# uvir-carrier-r1-easyeda-standard-schemat.net
KiCad netlist of a schematic drawn in EasyEDA
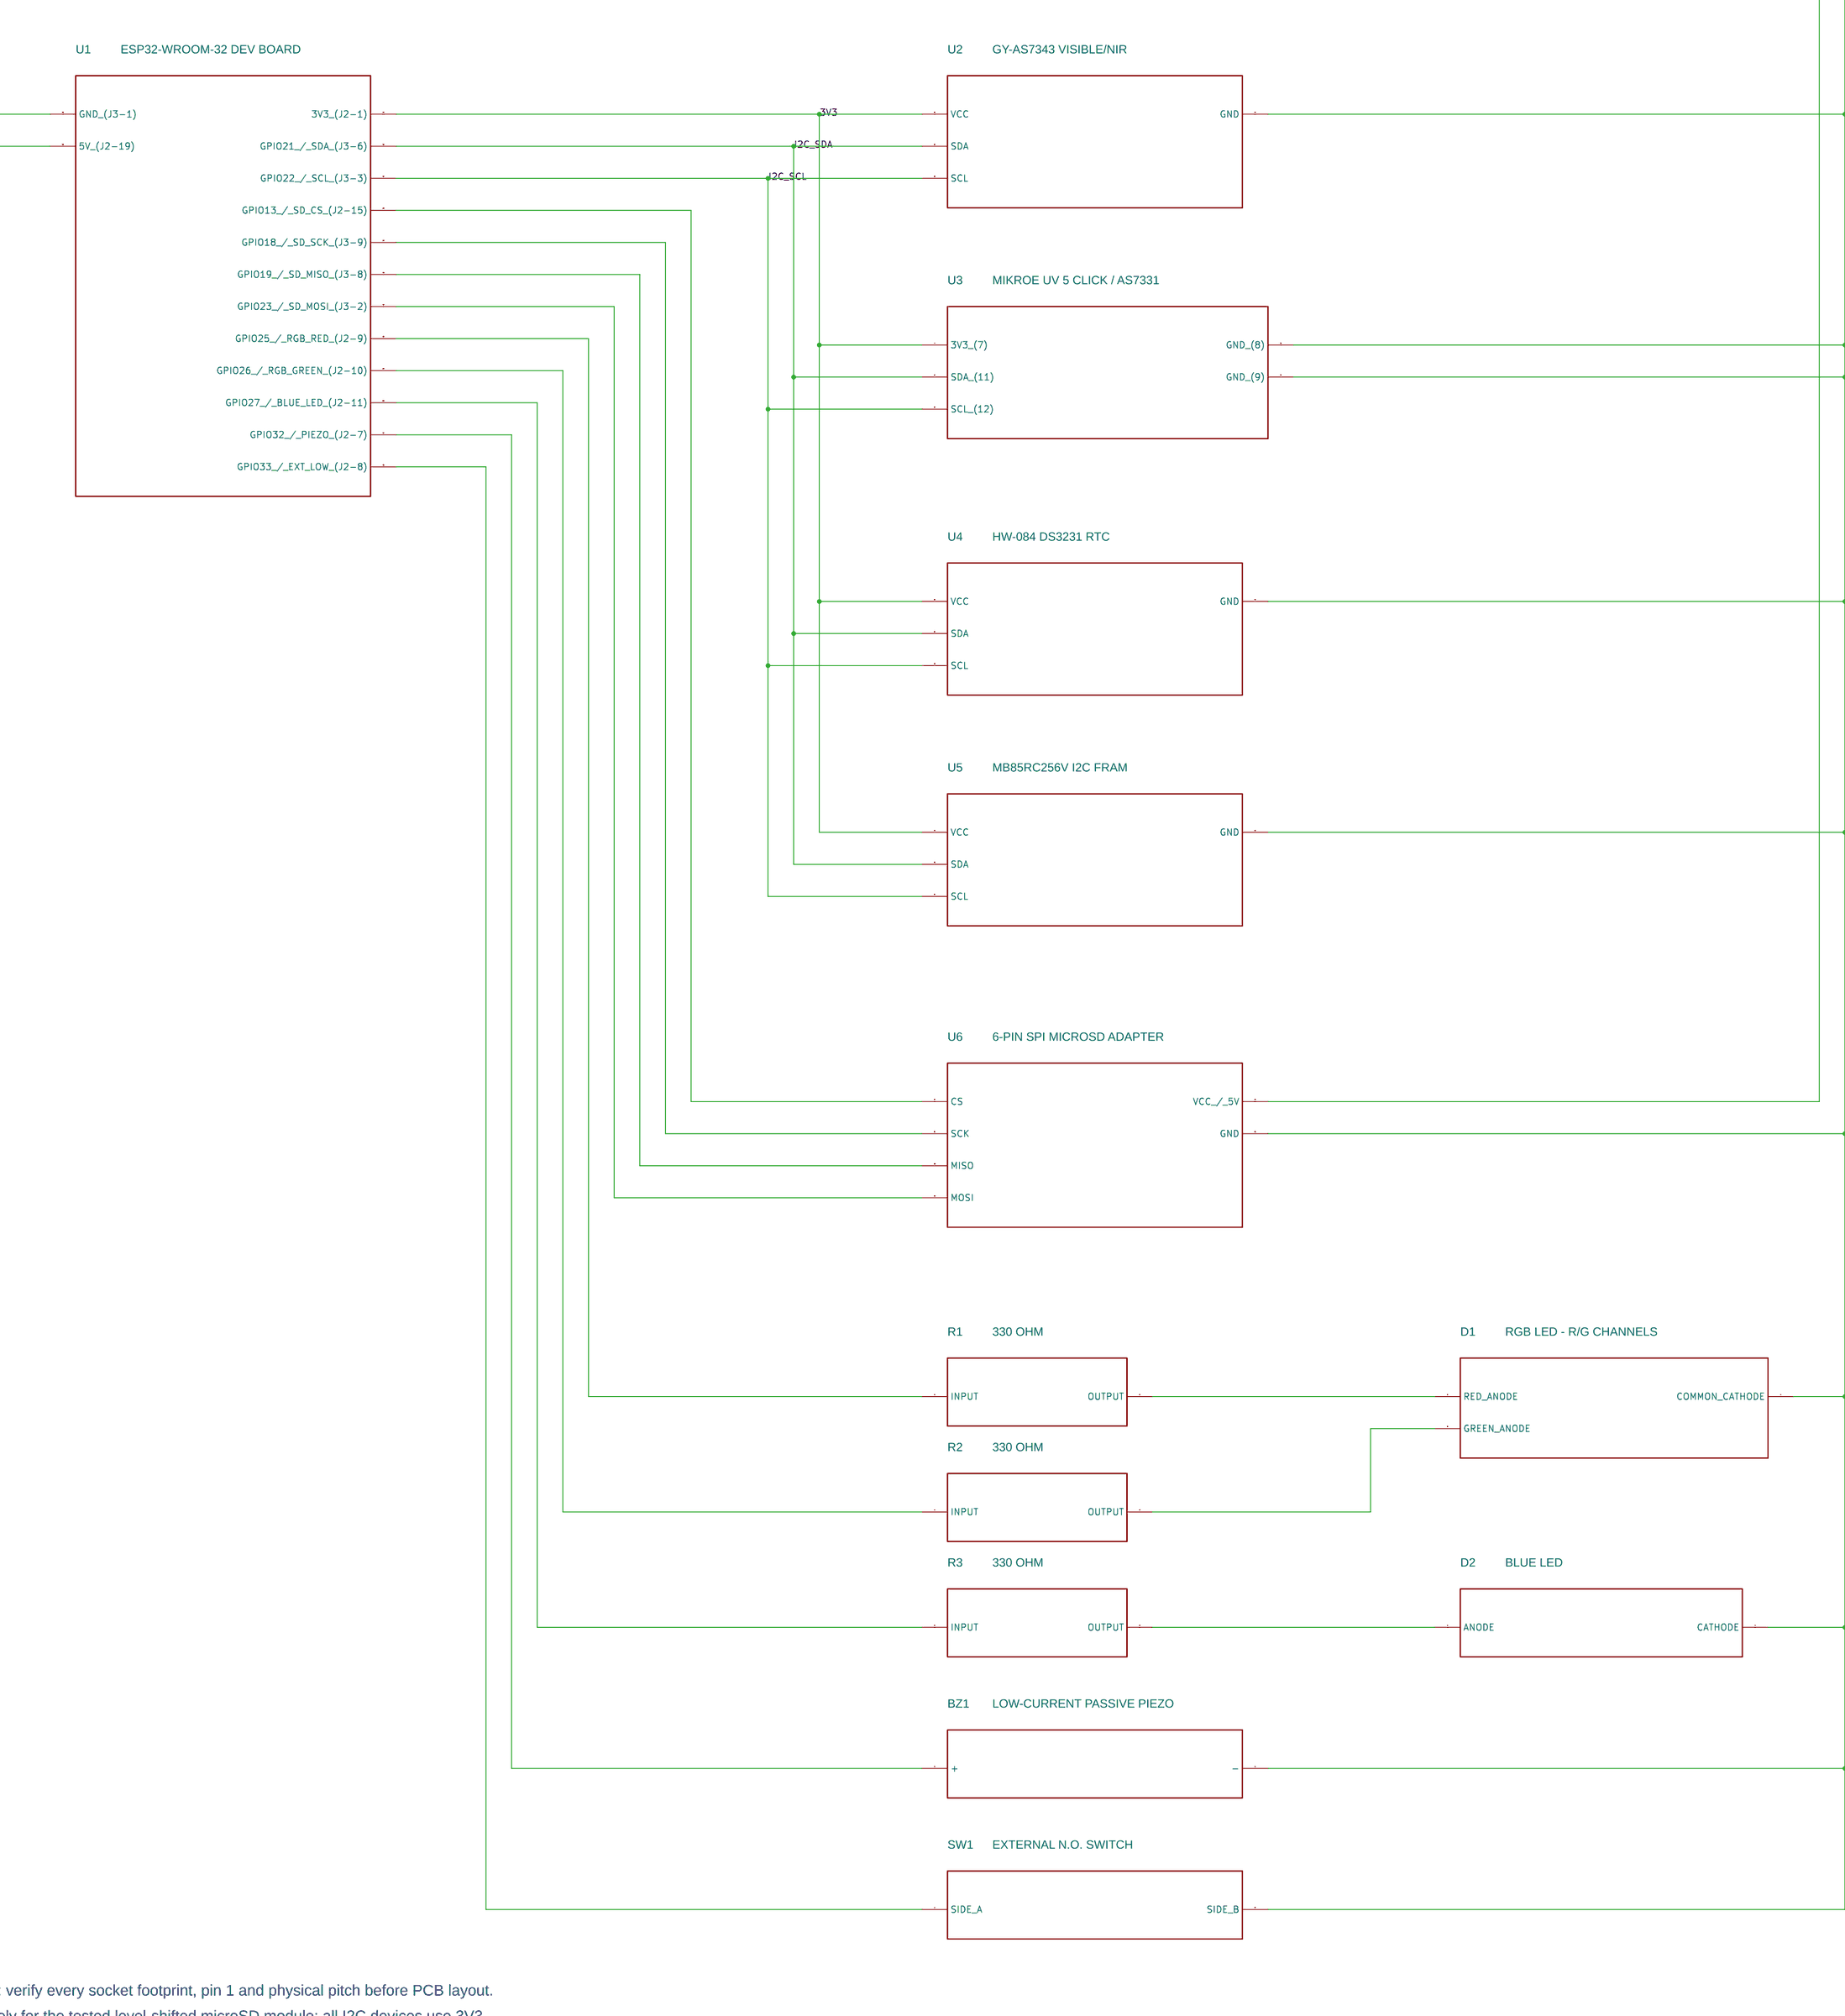
[diagram p0: schematic sheet]

(export (version "E")
  (design (tool "Eeschema 10.0.6"))
  (components
    (comp (ref "BZ1") (value "LOW-CURRENT PASSIVE PIEZO") (libsource (lib "") (part "Unknown_900_1550")))
    (comp (ref "D1") (value "RGB LED - R/G CHANNELS") (libsource (lib "") (part "Unknown_1300_1260")))
    (comp (ref "D2") (value "BLUE LED") (libsource (lib "") (part "Unknown_1300_1440")))
    (comp (ref "R1") (value "330 OHM") (libsource (lib "") (part "Unknown_900_1260")))
    (comp (ref "R2") (value "330 OHM") (libsource (lib "") (part "Unknown_900_1350")))
    (comp (ref "R3") (value "330 OHM") (libsource (lib "") (part "Unknown_900_1440")))
    (comp (ref "SW1") (value "EXTERNAL N.O. SWITCH") (libsource (lib "") (part "Unknown_900_1660")))
    (comp (ref "U1") (value "ESP32-WROOM-32 DEV BOARD") (libsource (lib "") (part "Unknown_220_260")))
    (comp (ref "U2") (value "GY-AS7343 VISIBLE/NIR") (libsource (lib "") (part "Unknown_900_260")))
    (comp (ref "U3") (value "MIKROE UV 5 CLICK / AS7331") (libsource (lib "") (part "Unknown_900_440")))
    (comp (ref "U4") (value "HW-084 DS3231 RTC") (libsource (lib "") (part "Unknown_900_640")))
    (comp (ref "U5") (value "MB85RC256V I2C FRAM") (libsource (lib "") (part "Unknown_900_820")))
    (comp (ref "U6") (value "6-PIN SPI MICROSD ADAPTER") (libsource (lib "") (part "Unknown_900_1030")))
  )
  (nets
    (net (code "1") (name "/3V3") (class "Default")
      (node (ref "U1") (pin "J2-1") (pinfunction "3V3_(J2-1)_J2-1") (pintype "unspecified"))
      (node (ref "U2") (pin "VCC") (pinfunction "VCC_VCC") (pintype "unspecified"))
      (node (ref "U3") (pin "7") (pinfunction "3V3_(7)_7") (pintype "unspecified"))
      (node (ref "U4") (pin "VCC") (pinfunction "VCC_VCC") (pintype "unspecified"))
      (node (ref "U5") (pin "VCC") (pinfunction "VCC_VCC") (pintype "unspecified"))
    )
    (net (code "2") (name "/5V_USB") (class "Default")
      (node (ref "U1") (pin "J2-19") (pinfunction "5V_(J2-19)_J2-19") (pintype "unspecified"))
      (node (ref "U6") (pin "VCC") (pinfunction "VCC_/_5V_VCC") (pintype "unspecified"))
    )
    (net (code "3") (name "/GND") (class "Default")
      (node (ref "BZ1") (pin "2") (pinfunction "-_2") (pintype "unspecified"))
      (node (ref "D1") (pin "K") (pinfunction "COMMON_CATHODE_K") (pintype "unspecified"))
      (node (ref "D2") (pin "K") (pinfunction "CATHODE_K") (pintype "unspecified"))
      (node (ref "SW1") (pin "B") (pinfunction "SIDE_B_B") (pintype "unspecified"))
      (node (ref "U1") (pin "J3-1") (pinfunction "GND_(J3-1)_J3-1") (pintype "unspecified"))
      (node (ref "U2") (pin "GND") (pinfunction "GND_GND") (pintype "unspecified"))
      (node (ref "U3") (pin "8") (pinfunction "GND_(8)_8") (pintype "unspecified"))
      (node (ref "U3") (pin "9") (pinfunction "GND_(9)_9") (pintype "unspecified"))
      (node (ref "U4") (pin "GND") (pinfunction "GND_GND") (pintype "unspecified"))
      (node (ref "U5") (pin "GND") (pinfunction "GND_GND") (pintype "unspecified"))
      (node (ref "U6") (pin "GND") (pinfunction "GND_GND") (pintype "unspecified"))
    )
    (net (code "4") (name "/I2C_SCL") (class "Default")
      (node (ref "U1") (pin "J3-3") (pinfunction "GPIO22_/_SCL_(J3-3)_J3-3") (pintype "unspecified"))
      (node (ref "U2") (pin "SCL") (pinfunction "SCL_SCL") (pintype "unspecified"))
      (node (ref "U3") (pin "12") (pinfunction "SCL_(12)_12") (pintype "unspecified"))
      (node (ref "U4") (pin "SCL") (pinfunction "SCL_SCL") (pintype "unspecified"))
      (node (ref "U5") (pin "SCL") (pinfunction "SCL_SCL") (pintype "unspecified"))
    )
    (net (code "5") (name "/I2C_SDA") (class "Default")
      (node (ref "U1") (pin "J3-6") (pinfunction "GPIO21_/_SDA_(J3-6)_J3-6") (pintype "unspecified"))
      (node (ref "U2") (pin "SDA") (pinfunction "SDA_SDA") (pintype "unspecified"))
      (node (ref "U3") (pin "11") (pinfunction "SDA_(11)_11") (pintype "unspecified"))
      (node (ref "U4") (pin "SDA") (pinfunction "SDA_SDA") (pintype "unspecified"))
      (node (ref "U5") (pin "SDA") (pinfunction "SDA_SDA") (pintype "unspecified"))
    )
    (net (code "6") (name "Net-(BZ1-+)") (class "Default")
      (node (ref "BZ1") (pin "1") (pinfunction "+_1") (pintype "unspecified"))
      (node (ref "U1") (pin "J2-7") (pinfunction "GPIO32_/_PIEZO_(J2-7)_J2-7") (pintype "unspecified"))
    )
    (net (code "7") (name "Net-(D1-GREEN_ANODE)") (class "Default")
      (node (ref "D1") (pin "G") (pinfunction "GREEN_ANODE_G") (pintype "unspecified"))
      (node (ref "R2") (pin "2") (pinfunction "OUTPUT_2") (pintype "unspecified"))
    )
    (net (code "8") (name "Net-(D1-RED_ANODE)") (class "Default")
      (node (ref "D1") (pin "R") (pinfunction "RED_ANODE_R") (pintype "unspecified"))
      (node (ref "R1") (pin "2") (pinfunction "OUTPUT_2") (pintype "unspecified"))
    )
    (net (code "9") (name "Net-(D2-ANODE)") (class "Default")
      (node (ref "D2") (pin "A") (pinfunction "ANODE_A") (pintype "unspecified"))
      (node (ref "R3") (pin "2") (pinfunction "OUTPUT_2") (pintype "unspecified"))
    )
    (net (code "10") (name "Net-(R1-INPUT)") (class "Default")
      (node (ref "R1") (pin "1") (pinfunction "INPUT_1") (pintype "unspecified"))
      (node (ref "U1") (pin "J2-9") (pinfunction "GPIO25_/_RGB_RED_(J2-9)_J2-9") (pintype "unspecified"))
    )
    (net (code "11") (name "Net-(R2-INPUT)") (class "Default")
      (node (ref "R2") (pin "1") (pinfunction "INPUT_1") (pintype "unspecified"))
      (node (ref "U1") (pin "J2-10") (pinfunction "GPIO26_/_RGB_GREEN_(J2-10)_J2-10") (pintype "unspecified"))
    )
    (net (code "12") (name "Net-(R3-INPUT)") (class "Default")
      (node (ref "R3") (pin "1") (pinfunction "INPUT_1") (pintype "unspecified"))
      (node (ref "U1") (pin "J2-11") (pinfunction "GPIO27_/_BLUE_LED_(J2-11)_J2-11") (pintype "unspecified"))
    )
    (net (code "13") (name "Net-(SW1-SIDE_A)") (class "Default")
      (node (ref "SW1") (pin "A") (pinfunction "SIDE_A_A") (pintype "unspecified"))
      (node (ref "U1") (pin "J2-8") (pinfunction "GPIO33_/_EXT_LOW_(J2-8)_J2-8") (pintype "unspecified"))
    )
    (net (code "14") (name "Net-(U1-GPIO13_{slash}_SD_CS_(J2-15))") (class "Default")
      (node (ref "U1") (pin "J2-15") (pinfunction "GPIO13_/_SD_CS_(J2-15)_J2-15") (pintype "unspecified"))
      (node (ref "U6") (pin "CS") (pinfunction "CS_CS") (pintype "unspecified"))
    )
    (net (code "15") (name "Net-(U1-GPIO18_{slash}_SD_SCK_(J3-9))") (class "Default")
      (node (ref "U1") (pin "J3-9") (pinfunction "GPIO18_/_SD_SCK_(J3-9)_J3-9") (pintype "unspecified"))
      (node (ref "U6") (pin "SCK") (pinfunction "SCK_SCK") (pintype "unspecified"))
    )
    (net (code "16") (name "Net-(U1-GPIO19_{slash}_SD_MISO_(J3-8))") (class "Default")
      (node (ref "U1") (pin "J3-8") (pinfunction "GPIO19_/_SD_MISO_(J3-8)_J3-8") (pintype "unspecified"))
      (node (ref "U6") (pin "MISO") (pinfunction "MISO_MISO") (pintype "unspecified"))
    )
    (net (code "17") (name "Net-(U1-GPIO23_{slash}_SD_MOSI_(J3-2))") (class "Default")
      (node (ref "U1") (pin "J3-2") (pinfunction "GPIO23_/_SD_MOSI_(J3-2)_J3-2") (pintype "unspecified"))
      (node (ref "U6") (pin "MOSI") (pinfunction "MOSI_MOSI") (pintype "unspecified"))
    )
  )
)
